# mother_card_04.net
KiCad netlist of a schematic drawn in EAGLE
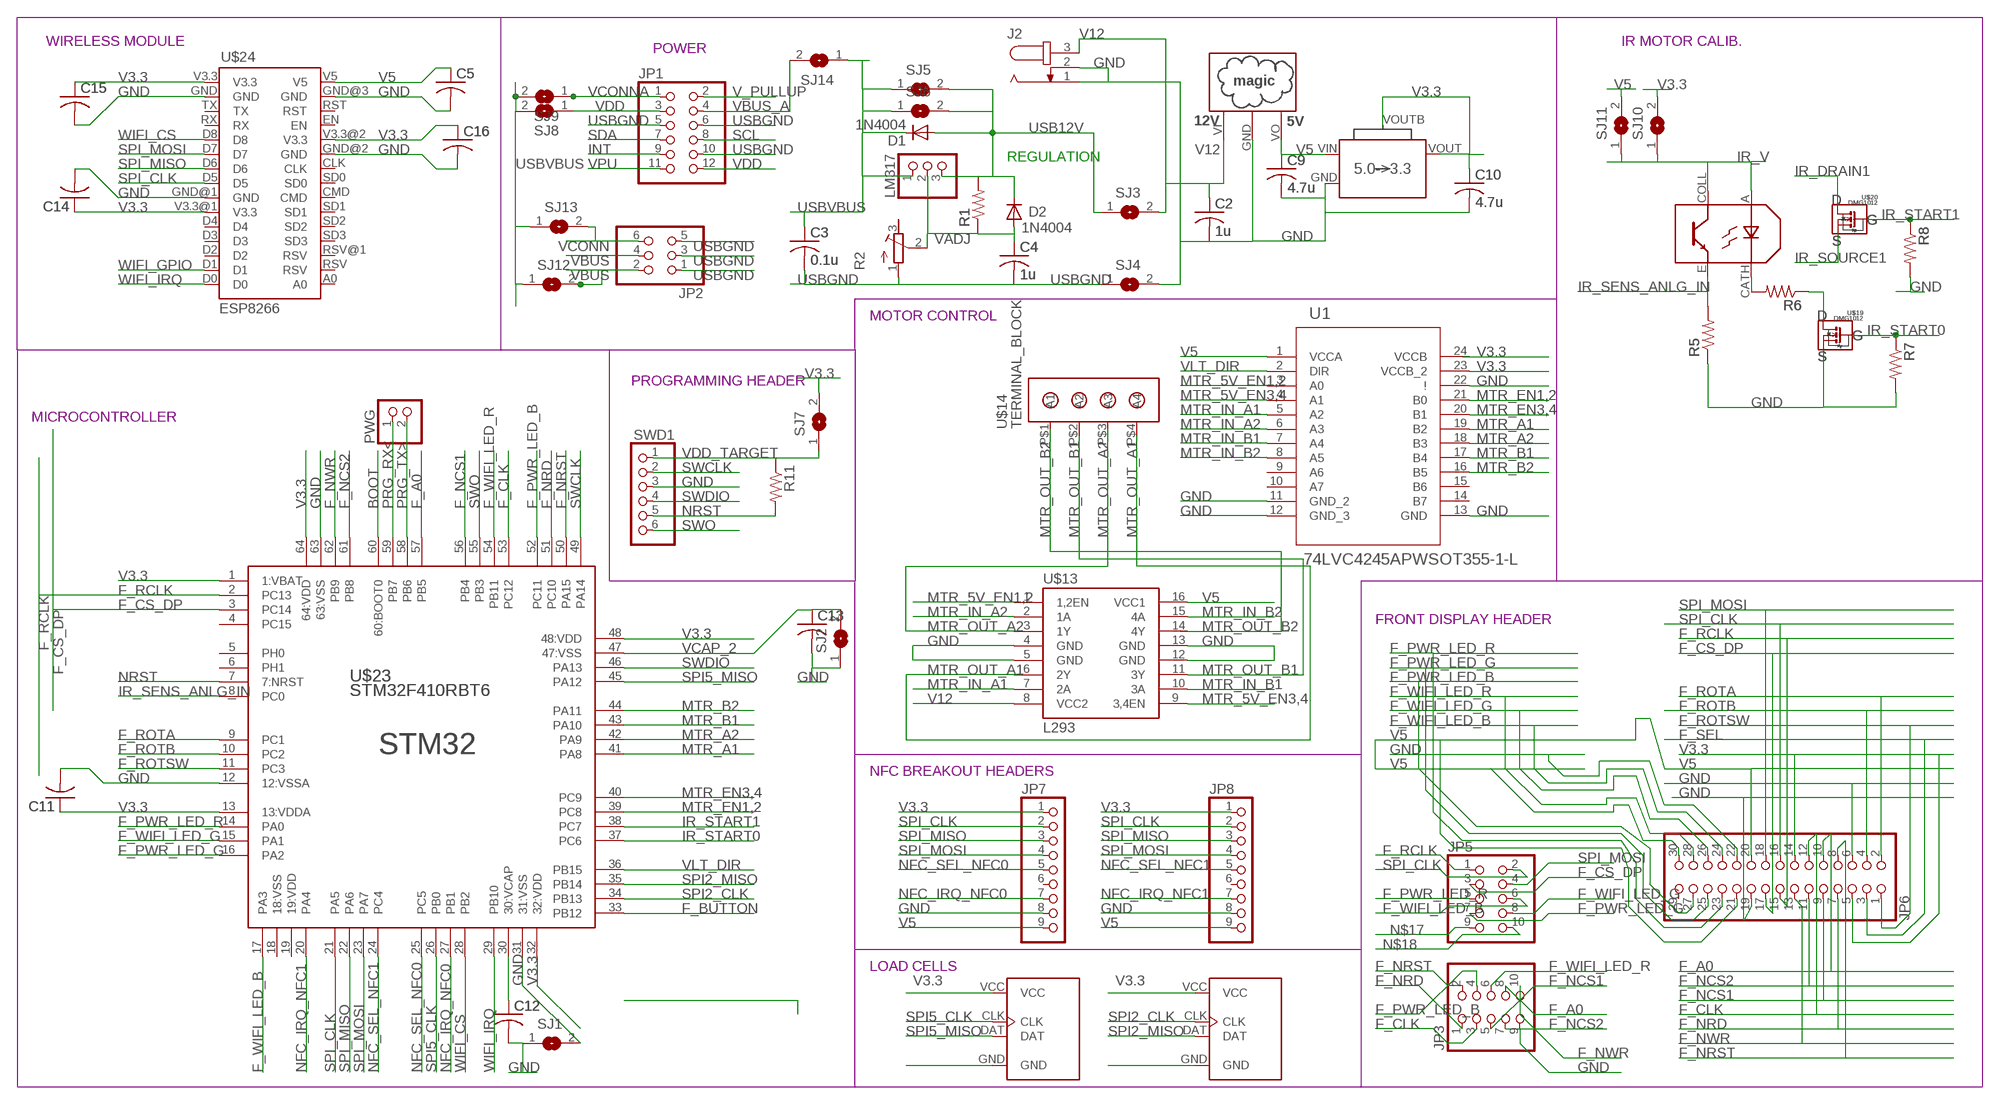
[diagram p0: schematic, sheet 1]

(export (version "E")
  (design (tool "Eeschema 10.0.6"))
  (components
    (comp (ref "C2")
      (value "1u")
      (footprint "eagle-import:C0805")
      (libsource (lib "eagle-import") (part "C-USC0805"))
    )
    (comp (ref "C3")
      (value "0.1u")
      (footprint "eagle-import:C0805")
      (libsource (lib "eagle-import") (part "C-USC0805"))
    )
    (comp (ref "C4")
      (value "1u")
      (footprint "eagle-import:C0805")
      (libsource (lib "eagle-import") (part "C-USC0805"))
    )
    (comp (ref "C5")
      (value "C-USC0805")
      (footprint "eagle-import:C0805")
      (libsource (lib "eagle-import") (part "C-USC0805"))
    )
    (comp (ref "C9")
      (value "4.7u")
      (footprint "eagle-import:C0805")
      (libsource (lib "eagle-import") (part "C-USC0805"))
    )
    (comp (ref "C10")
      (value "4.7u")
      (footprint "eagle-import:C0805")
      (libsource (lib "eagle-import") (part "C-USC0805"))
    )
    (comp (ref "C11")
      (value "C-USC0805")
      (footprint "eagle-import:C0805")
      (libsource (lib "eagle-import") (part "C-USC0805"))
    )
    (comp (ref "C12")
      (value "C-USC0805")
      (footprint "eagle-import:C0805")
      (libsource (lib "eagle-import") (part "C-USC0805"))
    )
    (comp (ref "C13")
      (value "C-USC0805")
      (footprint "eagle-import:C0805")
      (libsource (lib "eagle-import") (part "C-USC0805"))
    )
    (comp (ref "C14")
      (value "C-USC0805")
      (footprint "eagle-import:C0805")
      (libsource (lib "eagle-import") (part "C-USC0805"))
    )
    (comp (ref "C15")
      (value "C-USC0805")
      (footprint "eagle-import:C0805")
      (libsource (lib "eagle-import") (part "C-USC0805"))
    )
    (comp (ref "C16")
      (value "C-USC0805")
      (footprint "eagle-import:C0805")
      (libsource (lib "eagle-import") (part "C-USC0805"))
    )
    (comp (ref "D1")
      (value "1N4004")
      (footprint "eagle-import:DO41-10")
      (libsource (lib "eagle-import") (part "1N4004"))
    )
    (comp (ref "D2")
      (value "1N4004")
      (footprint "eagle-import:DO41-10")
      (libsource (lib "eagle-import") (part "1N4004"))
    )
    (comp (ref "J2")
      (value "JACK-PLUG0")
      (footprint "eagle-import:SPC4077")
      (libsource (lib "eagle-import") (part "JACK-PLUG0"))
    )
    (comp (ref "JP1")
      (value "PINHD-2X6")
      (footprint "eagle-import:2X06")
      (libsource (lib "eagle-import") (part "PINHD-2X6"))
    )
    (comp (ref "JP2")
      (value "PINHD-2X3")
      (footprint "eagle-import:2X03")
      (libsource (lib "eagle-import") (part "PINHD-2X3"))
    )
    (comp (ref "JP3")
      (value "PINHD-2X5")
      (footprint "eagle-import:2X05")
      (libsource (lib "eagle-import") (part "PINHD-2X5"))
    )
    (comp (ref "JP5")
      (value "PINHD-2X5")
      (footprint "eagle-import:2X05")
      (libsource (lib "eagle-import") (part "PINHD-2X5"))
    )
    (comp (ref "JP6")
      (value "PINHD-2X15/SOCK")
      (footprint "eagle-import:2X15_SOCK")
      (libsource (lib "eagle-import") (part "PINHD-2X15/SOCK"))
    )
    (comp (ref "JP7")
      (value "PINHD-1X9/90")
      (footprint "eagle-import:1X09_90")
      (libsource (lib "eagle-import") (part "PINHD-1X9/90"))
    )
    (comp (ref "JP8")
      (value "PINHD-1X9/90")
      (footprint "eagle-import:1X09_90")
      (libsource (lib "eagle-import") (part "PINHD-1X9/90"))
    )
    (comp (ref "LM317")
      (value "PINHD-1X3")
      (footprint "eagle-import:1X03")
      (libsource (lib "eagle-import") (part "PINHD-1X3"))
    )
    (comp (ref "PWG")
      (value "PINHD-1X2")
      (footprint "eagle-import:1X02")
      (libsource (lib "eagle-import") (part "PINHD-1X2"))
    )
    (comp (ref "R1")
      (value "R-US_R0805")
      (footprint "eagle-import:R0805")
      (libsource (lib "eagle-import") (part "seniorDesign_R-US_R0805"))
    )
    (comp (ref "R2")
      (value "R-TRIMM64W")
      (footprint "eagle-import:RTRIM64W")
      (libsource (lib "eagle-import") (part "R-TRIMM64W"))
    )
    (comp (ref "R5")
      (value "R-US_R0805")
      (footprint "eagle-import:R0805")
      (libsource (lib "eagle-import") (part "seniorDesign_R-US_R0805"))
    )
    (comp (ref "R6")
      (value "R-US_R0805")
      (footprint "eagle-import:R0805")
      (libsource (lib "eagle-import") (part "seniorDesign_R-US_R0805"))
    )
    (comp (ref "R7")
      (value "R-US_R0805")
      (footprint "eagle-import:R0805")
      (libsource (lib "eagle-import") (part "seniorDesign_R-US_R0805"))
    )
    (comp (ref "R8")
      (value "R-US_R0805")
      (footprint "eagle-import:R0805")
      (libsource (lib "eagle-import") (part "seniorDesign_R-US_R0805"))
    )
    (comp (ref "R11")
      (value "R-US_R0805")
      (footprint "eagle-import:R0805")
      (libsource (lib "eagle-import") (part "R-US_R0805"))
    )
    (comp (ref "SJ1") (value "SJ") (footprint "eagle-import:SJ") (libsource (lib "eagle-import") (part "SJ")))
    (comp (ref "SJ2") (value "SJ") (footprint "eagle-import:SJ") (libsource (lib "eagle-import") (part "SJ")))
    (comp (ref "SJ3") (value "SJ") (footprint "eagle-import:SJ") (libsource (lib "eagle-import") (part "SJ")))
    (comp (ref "SJ4") (value "SJ") (footprint "eagle-import:SJ") (libsource (lib "eagle-import") (part "SJ")))
    (comp (ref "SJ5") (value "SJ") (footprint "eagle-import:SJ") (libsource (lib "eagle-import") (part "SJ")))
    (comp (ref "SJ6") (value "SJ") (footprint "eagle-import:SJ") (libsource (lib "eagle-import") (part "SJ")))
    (comp (ref "SJ7") (value "SJ") (footprint "eagle-import:SJ") (libsource (lib "eagle-import") (part "SJ")))
    (comp (ref "SJ8") (value "SJ") (footprint "eagle-import:SJ") (libsource (lib "eagle-import") (part "SJ")))
    (comp (ref "SJ9") (value "SJ") (footprint "eagle-import:SJ") (libsource (lib "eagle-import") (part "SJ")))
    (comp (ref "SJ10")
      (value "SJ")
      (footprint "eagle-import:SJ")
      (libsource (lib "eagle-import") (part "SJ"))
    )
    (comp (ref "SJ11")
      (value "SJ")
      (footprint "eagle-import:SJ")
      (libsource (lib "eagle-import") (part "SJ"))
    )
    (comp (ref "SJ12")
      (value "SJ")
      (footprint "eagle-import:SJ")
      (libsource (lib "eagle-import") (part "SJ"))
    )
    (comp (ref "SJ13")
      (value "SJ")
      (footprint "eagle-import:SJ")
      (libsource (lib "eagle-import") (part "SJ"))
    )
    (comp (ref "SJ14")
      (value "SJ")
      (footprint "eagle-import:SJ")
      (libsource (lib "eagle-import") (part "SJ"))
    )
    (comp (ref "SWD1")
      (value "PINHD-1X6")
      (footprint "eagle-import:1X06")
      (libsource (lib "eagle-import") (part "PINHD-1X6"))
    )
    (comp (ref "U$13")
      (value "L293")
      (footprint "eagle-import:DIL16")
      (libsource (lib "eagle-import") (part "L293"))
    )
    (comp (ref "U$14")
      (value "TERMINAL_BLOCK")
      (footprint "eagle-import:1X4_BLOCK")
      (libsource (lib "eagle-import") (part "TERMINAL_BLOCK"))
    )
    (comp (ref "U$15")
      (value "AP2114H")
      (footprint "eagle-import:AP2114H")
      (libsource (lib "eagle-import") (part "AP2114H"))
    )
    (comp (ref "U$16")
      (value "OKI-78SR-W36")
      (footprint "eagle-import:SIP3")
      (libsource (lib "eagle-import") (part "OKI-78SR-W36"))
    )
    (comp (ref "U$18")
      (value "TCRT5000")
      (footprint "eagle-import:TCRT5000")
      (libsource (lib "eagle-import") (part "TCRT5000"))
    )
    (comp (ref "U$19")
      (value "DMG1012")
      (footprint "eagle-import:SOT323")
      (libsource (lib "eagle-import") (part "DMG1012"))
    )
    (comp (ref "U$20")
      (value "DMG1012")
      (footprint "eagle-import:SOT323")
      (libsource (lib "eagle-import") (part "DMG1012"))
    )
    (comp (ref "U$21")
      (value "HX711")
      (footprint "eagle-import:HX711")
      (libsource (lib "eagle-import") (part "HX711"))
    )
    (comp (ref "U$22")
      (value "HX711")
      (footprint "eagle-import:HX711")
      (libsource (lib "eagle-import") (part "HX711"))
    )
    (comp (ref "U$23")
      (value "STM32F410RBT6")
      (footprint "eagle-import:QFP50P1200X1200X160-64N")
      (libsource (lib "eagle-import") (part "STM32F410RBT6"))
    )
    (comp (ref "U$24")
      (value "ESP8266")
      (footprint "eagle-import:ESP8266")
      (libsource (lib "eagle-import") (part "ESP8266"))
    )
    (comp (ref "U1")
      (value "74LVC4245APWSOT355-1-L")
      (footprint "eagle-import:SOT355-1-L")
      (fields (field (name "MANUFACTURER_PART_NUMBER") "74LVC4245APW"))
      (libsource (lib "eagle-import") (part "74LVC4245APWSOT355-1-L"))
    )
  )
  (nets
    (net (code "1") (name "/BOOT") (class "Default")
      (node (ref "U$23") (pin "60") (pinfunction "60:BOOT0_60") (pintype "bidirectional"))
    )
    (net (code "2") (name "/F_A0") (class "Default")
      (node (ref "JP3") (pin "8") (pinfunction "8_8") (pintype "passive"))
      (node (ref "JP6") (pin "10") (pinfunction "10_10") (pintype "passive"))
      (node (ref "U$23") (pin "57") (pinfunction "PB5_57") (pintype "bidirectional"))
    )
    (net (code "3") (name "/F_BUTTON") (class "Default")
      (node (ref "U$23") (pin "33") (pinfunction "PB12_33") (pintype "bidirectional"))
    )
    (net (code "4") (name "/F_CLK") (class "Default")
      (node (ref "JP3") (pin "3") (pinfunction "3_3") (pintype "passive"))
      (node (ref "JP6") (pin "12") (pinfunction "12_12") (pintype "passive"))
      (node (ref "U$23") (pin "53") (pinfunction "PC12_53") (pintype "bidirectional"))
    )
    (net (code "5") (name "/F_CS_DP") (class "Default")
      (node (ref "JP5") (pin "3") (pinfunction "3_3") (pintype "passive"))
      (node (ref "JP6") (pin "17") (pinfunction "17_17") (pintype "passive"))
      (node (ref "U$23") (pin "3") (pinfunction "PC14_3") (pintype "bidirectional"))
    )
    (net (code "6") (name "/F_NCS1") (class "Default")
      (node (ref "JP3") (pin "5") (pinfunction "5_5") (pintype "passive"))
      (node (ref "JP6") (pin "9") (pinfunction "9_9") (pintype "passive"))
      (node (ref "U$23") (pin "56") (pinfunction "PB4_56") (pintype "bidirectional"))
    )
    (net (code "7") (name "/F_NCS2") (class "Default")
      (node (ref "JP3") (pin "7") (pinfunction "7_7") (pintype "passive"))
      (node (ref "JP6") (pin "11") (pinfunction "11_11") (pintype "passive"))
      (node (ref "U$23") (pin "61") (pinfunction "PB8_61") (pintype "bidirectional"))
    )
    (net (code "8") (name "/F_NRD") (class "Default")
      (node (ref "JP3") (pin "1") (pinfunction "1_1") (pintype "passive"))
      (node (ref "JP6") (pin "7") (pinfunction "7_7") (pintype "passive"))
      (node (ref "U$23") (pin "51") (pinfunction "PC10_51") (pintype "bidirectional"))
    )
    (net (code "9") (name "/F_NRST") (class "Default")
      (node (ref "JP3") (pin "2") (pinfunction "2_2") (pintype "passive"))
      (node (ref "JP6") (pin "8") (pinfunction "8_8") (pintype "passive"))
      (node (ref "U$23") (pin "50") (pinfunction "PA15_50") (pintype "bidirectional"))
    )
    (net (code "10") (name "/F_NWR") (class "Default")
      (node (ref "JP3") (pin "10") (pinfunction "10_10") (pintype "passive"))
      (node (ref "JP6") (pin "13") (pinfunction "13_13") (pintype "passive"))
      (node (ref "U$23") (pin "62") (pinfunction "PB9_62") (pintype "bidirectional"))
    )
    (net (code "11") (name "/F_PWR_LED_B") (class "Default")
      (node (ref "JP3") (pin "4") (pinfunction "4_4") (pintype "passive"))
      (node (ref "JP6") (pin "27") (pinfunction "27_27") (pintype "passive"))
      (node (ref "U$23") (pin "52") (pinfunction "PC11_52") (pintype "bidirectional"))
    )
    (net (code "12") (name "/F_PWR_LED_G") (class "Default")
      (node (ref "JP5") (pin "7") (pinfunction "7_7") (pintype "passive"))
      (node (ref "JP6") (pin "25") (pinfunction "25_25") (pintype "passive"))
      (node (ref "U$23") (pin "16") (pinfunction "PA2_16") (pintype "bidirectional"))
    )
    (net (code "13") (name "/F_PWR_LED_R") (class "Default")
      (node (ref "JP5") (pin "5") (pinfunction "5_5") (pintype "passive"))
      (node (ref "JP6") (pin "23") (pinfunction "23_23") (pintype "passive"))
      (node (ref "U$23") (pin "14") (pinfunction "PA0_14") (pintype "bidirectional"))
    )
    (net (code "14") (name "/F_RCLK") (class "Default")
      (node (ref "JP5") (pin "1") (pinfunction "1_1") (pintype "passive"))
      (node (ref "JP6") (pin "15") (pinfunction "15_15") (pintype "passive"))
      (node (ref "U$23") (pin "2") (pinfunction "PC13_2") (pintype "bidirectional"))
    )
    (net (code "15") (name "/F_ROTA") (class "Default")
      (node (ref "JP6") (pin "2") (pinfunction "2_2") (pintype "passive"))
      (node (ref "U$23") (pin "9") (pinfunction "PC1_9") (pintype "bidirectional"))
    )
    (net (code "16") (name "/F_ROTB") (class "Default")
      (node (ref "JP6") (pin "4") (pinfunction "4_4") (pintype "passive"))
      (node (ref "U$23") (pin "10") (pinfunction "PC2_10") (pintype "bidirectional"))
    )
    (net (code "17") (name "/F_ROTSW") (class "Default")
      (node (ref "JP6") (pin "1") (pinfunction "1_1") (pintype "passive"))
      (node (ref "U$23") (pin "11") (pinfunction "PC3_11") (pintype "bidirectional"))
    )
    (net (code "18") (name "/F_SEL") (class "Default")
      (node (ref "JP6") (pin "3") (pinfunction "3_3") (pintype "passive"))
    )
    (net (code "19") (name "/F_WIFI_LED_B") (class "Default")
      (node (ref "JP5") (pin "6") (pinfunction "6_6") (pintype "passive"))
      (node (ref "JP6") (pin "24") (pinfunction "24_24") (pintype "passive"))
      (node (ref "U$23") (pin "17") (pinfunction "PA3_17") (pintype "bidirectional"))
    )
    (net (code "20") (name "/F_WIFI_LED_G") (class "Default")
      (node (ref "JP5") (pin "8") (pinfunction "8_8") (pintype "passive"))
      (node (ref "JP6") (pin "26") (pinfunction "26_26") (pintype "passive"))
      (node (ref "U$23") (pin "15") (pinfunction "PA1_15") (pintype "bidirectional"))
    )
    (net (code "21") (name "/F_WIFI_LED_R") (class "Default")
      (node (ref "JP3") (pin "6") (pinfunction "6_6") (pintype "passive"))
      (node (ref "JP6") (pin "28") (pinfunction "28_28") (pintype "passive"))
      (node (ref "U$23") (pin "54") (pinfunction "PB11_54") (pintype "bidirectional"))
    )
    (net (code "22") (name "/GND") (class "Default")
      (node (ref "C10") (pin "2") (pinfunction "2_2") (pintype "passive"))
      (node (ref "C11") (pin "2") (pinfunction "2_2") (pintype "passive"))
      (node (ref "C12") (pin "2") (pinfunction "2_2") (pintype "passive"))
      (node (ref "C13") (pin "2") (pinfunction "2_2") (pintype "passive"))
      (node (ref "C14") (pin "2") (pinfunction "2_2") (pintype "passive"))
      (node (ref "C15") (pin "2") (pinfunction "2_2") (pintype "passive"))
      (node (ref "C16") (pin "2") (pinfunction "2_2") (pintype "passive"))
      (node (ref "C2") (pin "2") (pinfunction "2_2") (pintype "passive"))
      (node (ref "C5") (pin "2") (pinfunction "2_2") (pintype "passive"))
      (node (ref "C9") (pin "2") (pinfunction "2_2") (pintype "passive"))
      (node (ref "J2") (pin "1") (pinfunction "1_1") (pintype "passive"))
      (node (ref "J2") (pin "2") (pinfunction "2_2") (pintype "passive"))
      (node (ref "JP3") (pin "9") (pinfunction "9_9") (pintype "passive"))
      (node (ref "JP6") (pin "19") (pinfunction "19_19") (pintype "passive"))
      (node (ref "JP6") (pin "22") (pinfunction "22_22") (pintype "passive"))
      (node (ref "JP6") (pin "6") (pinfunction "6_6") (pintype "passive"))
      (node (ref "JP7") (pin "8") (pinfunction "8_8") (pintype "passive"))
      (node (ref "JP8") (pin "8") (pinfunction "8_8") (pintype "passive"))
      (node (ref "R5") (pin "1") (pinfunction "1_1") (pintype "passive"))
      (node (ref "R7") (pin "2") (pinfunction "2_2") (pintype "passive"))
      (node (ref "R8") (pin "2") (pinfunction "2_2") (pintype "passive"))
      (node (ref "SJ1") (pin "1") (pinfunction "1_1") (pintype "passive"))
      (node (ref "SJ1") (pin "2") (pinfunction "2_2") (pintype "passive"))
      (node (ref "SJ2") (pin "1") (pinfunction "1_1") (pintype "passive"))
      (node (ref "SJ4") (pin "2") (pinfunction "2_2") (pintype "passive"))
      (node (ref "SWD1") (pin "3") (pinfunction "3_3") (pintype "passive"))
      (node (ref "U$13") (pin "12") (pinfunction "GND_12") (pintype "bidirectional"))
      (node (ref "U$13") (pin "13") (pinfunction "GND_13") (pintype "bidirectional"))
      (node (ref "U$13") (pin "4") (pinfunction "GND_4") (pintype "bidirectional"))
      (node (ref "U$13") (pin "5") (pinfunction "GND_5") (pintype "bidirectional"))
      (node (ref "U$15") (pin "GND") (pinfunction "GND_GND") (pintype "power_in"))
      (node (ref "U$16") (pin "GND") (pinfunction "P$2_GND") (pintype "power_in"))
      (node (ref "U$19") (pin "S") (pinfunction "S_S") (pintype "bidirectional"))
      (node (ref "U$21") (pin "GND") (pinfunction "GND_GND") (pintype "power_in"))
      (node (ref "U$22") (pin "GND") (pinfunction "GND_GND") (pintype "power_in"))
      (node (ref "U$23") (pin "12") (pinfunction "12:VSSA_12") (pintype "bidirectional"))
      (node (ref "U$23") (pin "31") (pinfunction "31:VSS_31") (pintype "bidirectional"))
      (node (ref "U$23") (pin "63") (pinfunction "63:VSS_63") (pintype "bidirectional"))
      (node (ref "U$24") (pin "GND") (pinfunction "GND_GND") (pintype "bidirectional"))
      (node (ref "U$24") (pin "GND@1") (pinfunction "GND_GND@1") (pintype "bidirectional"))
      (node (ref "U$24") (pin "GND@2") (pinfunction "GND_GND@2") (pintype "bidirectional"))
      (node (ref "U$24") (pin "GND@3") (pinfunction "GND_GND@3") (pintype "bidirectional"))
      (node (ref "U1") (pin "11") (pinfunction "GND_2_11") (pintype "power_in"))
      (node (ref "U1") (pin "12") (pinfunction "GND_3_12") (pintype "power_in"))
      (node (ref "U1") (pin "13") (pinfunction "GND_13") (pintype "power_in"))
      (node (ref "U1") (pin "22") (pinfunction "~_22") (pintype "input"))
    )
    (net (code "23") (name "/INT") (class "Default")
      (node (ref "JP1") (pin "9") (pinfunction "9_9") (pintype "passive"))
    )
    (net (code "24") (name "/IR_DRAIN1") (class "Default")
      (node (ref "U$20") (pin "D") (pinfunction "D_D") (pintype "bidirectional"))
    )
    (net (code "25") (name "/IR_SENS_ANLG_IN") (class "Default")
      (node (ref "R5") (pin "2") (pinfunction "2_2") (pintype "passive"))
      (node (ref "U$18") (pin "E") (pinfunction "E_E") (pintype "bidirectional"))
      (node (ref "U$23") (pin "8") (pinfunction "PC0_8") (pintype "bidirectional"))
    )
    (net (code "26") (name "/IR_SOURCE1") (class "Default")
      (node (ref "U$20") (pin "S") (pinfunction "S_S") (pintype "bidirectional"))
    )
    (net (code "27") (name "/IR_START0") (class "Default")
      (node (ref "R7") (pin "1") (pinfunction "1_1") (pintype "passive"))
      (node (ref "U$19") (pin "G") (pinfunction "G_G") (pintype "bidirectional"))
      (node (ref "U$23") (pin "37") (pinfunction "PC6_37") (pintype "bidirectional"))
    )
    (net (code "28") (name "/IR_START1") (class "Default")
      (node (ref "R8") (pin "1") (pinfunction "1_1") (pintype "passive"))
      (node (ref "U$20") (pin "G") (pinfunction "G_G") (pintype "bidirectional"))
      (node (ref "U$23") (pin "38") (pinfunction "PC7_38") (pintype "bidirectional"))
    )
    (net (code "29") (name "/IR_V") (class "Default")
      (node (ref "SJ10") (pin "1") (pinfunction "1_1") (pintype "passive"))
      (node (ref "SJ11") (pin "1") (pinfunction "1_1") (pintype "passive"))
      (node (ref "U$18") (pin "A") (pinfunction "A_A") (pintype "bidirectional"))
      (node (ref "U$18") (pin "COLL") (pinfunction "COLL_COLL") (pintype "bidirectional"))
    )
    (net (code "30") (name "/MTR_5V_EN1,2") (class "Default")
      (node (ref "U$13") (pin "1") (pinfunction "1,2EN_1") (pintype "bidirectional"))
      (node (ref "U1") (pin "3") (pinfunction "A0_3") (pintype "bidirectional"))
    )
    (net (code "31") (name "/MTR_5V_EN3,4") (class "Default")
      (node (ref "U$13") (pin "9") (pinfunction "3,4EN_9") (pintype "bidirectional"))
      (node (ref "U1") (pin "4") (pinfunction "A1_4") (pintype "bidirectional"))
    )
    (net (code "32") (name "/MTR_A1") (class "Default")
      (node (ref "U$23") (pin "41") (pinfunction "PA8_41") (pintype "bidirectional"))
      (node (ref "U1") (pin "19") (pinfunction "B2_19") (pintype "bidirectional"))
    )
    (net (code "33") (name "/MTR_A2") (class "Default")
      (node (ref "U$23") (pin "42") (pinfunction "PA9_42") (pintype "bidirectional"))
      (node (ref "U1") (pin "18") (pinfunction "B3_18") (pintype "bidirectional"))
    )
    (net (code "34") (name "/MTR_B1") (class "Default")
      (node (ref "U$23") (pin "43") (pinfunction "PA10_43") (pintype "bidirectional"))
      (node (ref "U1") (pin "17") (pinfunction "B4_17") (pintype "bidirectional"))
    )
    (net (code "35") (name "/MTR_B2") (class "Default")
      (node (ref "U$23") (pin "44") (pinfunction "PA11_44") (pintype "bidirectional"))
      (node (ref "U1") (pin "16") (pinfunction "B5_16") (pintype "bidirectional"))
    )
    (net (code "36") (name "/MTR_EN1,2") (class "Default")
      (node (ref "U$23") (pin "39") (pinfunction "PC8_39") (pintype "bidirectional"))
      (node (ref "U1") (pin "21") (pinfunction "B0_21") (pintype "bidirectional"))
    )
    (net (code "37") (name "/MTR_EN3,4") (class "Default")
      (node (ref "U$23") (pin "40") (pinfunction "PC9_40") (pintype "bidirectional"))
      (node (ref "U1") (pin "20") (pinfunction "B1_20") (pintype "bidirectional"))
    )
    (net (code "38") (name "/MTR_IN_A1") (class "Default")
      (node (ref "U$13") (pin "7") (pinfunction "2A_7") (pintype "bidirectional"))
      (node (ref "U1") (pin "5") (pinfunction "A2_5") (pintype "bidirectional"))
    )
    (net (code "39") (name "/MTR_IN_A2") (class "Default")
      (node (ref "U$13") (pin "2") (pinfunction "1A_2") (pintype "bidirectional"))
      (node (ref "U1") (pin "6") (pinfunction "A3_6") (pintype "bidirectional"))
    )
    (net (code "40") (name "/MTR_IN_B1") (class "Default")
      (node (ref "U$13") (pin "10") (pinfunction "3A_10") (pintype "bidirectional"))
      (node (ref "U1") (pin "7") (pinfunction "A4_7") (pintype "bidirectional"))
    )
    (net (code "41") (name "/MTR_IN_B2") (class "Default")
      (node (ref "U$13") (pin "15") (pinfunction "4A_15") (pintype "bidirectional"))
      (node (ref "U1") (pin "8") (pinfunction "A5_8") (pintype "bidirectional"))
    )
    (net (code "42") (name "/MTR_OUT_A1") (class "Default")
      (node (ref "U$13") (pin "6") (pinfunction "2Y_6") (pintype "bidirectional"))
      (node (ref "U$14") (pin "P$4") (pinfunction "A4_P$4") (pintype "bidirectional"))
    )
    (net (code "43") (name "/MTR_OUT_A2") (class "Default")
      (node (ref "U$13") (pin "3") (pinfunction "1Y_3") (pintype "bidirectional"))
      (node (ref "U$14") (pin "P$3") (pinfunction "A3_P$3") (pintype "bidirectional"))
    )
    (net (code "44") (name "/MTR_OUT_B1") (class "Default")
      (node (ref "U$13") (pin "11") (pinfunction "3Y_11") (pintype "bidirectional"))
      (node (ref "U$14") (pin "P$2") (pinfunction "A2_P$2") (pintype "bidirectional"))
    )
    (net (code "45") (name "/MTR_OUT_B2") (class "Default")
      (node (ref "U$13") (pin "14") (pinfunction "4Y_14") (pintype "bidirectional"))
      (node (ref "U$14") (pin "P$1") (pinfunction "A1_P$1") (pintype "bidirectional"))
    )
    (net (code "46") (name "/N$17") (class "Default")
      (node (ref "JP5") (pin "9") (pinfunction "9_9") (pintype "passive"))
    )
    (net (code "47") (name "/N$18") (class "Default")
      (node (ref "JP5") (pin "10") (pinfunction "10_10") (pintype "passive"))
    )
    (net (code "48") (name "/NFC_IRQ_NFC0") (class "Default")
      (node (ref "JP7") (pin "7") (pinfunction "7_7") (pintype "passive"))
      (node (ref "U$23") (pin "27") (pinfunction "PB1_27") (pintype "bidirectional"))
    )
    (net (code "49") (name "/NFC_IRQ_NFC1") (class "Default")
      (node (ref "JP8") (pin "7") (pinfunction "7_7") (pintype "passive"))
      (node (ref "U$23") (pin "20") (pinfunction "PA4_20") (pintype "bidirectional"))
    )
    (net (code "50") (name "/NFC_SEL_NFC0") (class "Default")
      (node (ref "JP7") (pin "5") (pinfunction "5_5") (pintype "passive"))
      (node (ref "U$23") (pin "25") (pinfunction "PC5_25") (pintype "bidirectional"))
    )
    (net (code "51") (name "/NFC_SEL_NFC1") (class "Default")
      (node (ref "JP8") (pin "5") (pinfunction "5_5") (pintype "passive"))
      (node (ref "U$23") (pin "24") (pinfunction "PC4_24") (pintype "bidirectional"))
    )
    (net (code "52") (name "/NRST") (class "Default")
      (node (ref "R11") (pin "2") (pinfunction "2_2") (pintype "passive"))
      (node (ref "SWD1") (pin "5") (pinfunction "5_5") (pintype "passive"))
      (node (ref "U$23") (pin "7") (pinfunction "7:NRST_7") (pintype "bidirectional"))
    )
    (net (code "53") (name "/PRG_RX<") (class "Default")
      (node (ref "PWG") (pin "1") (pinfunction "1_1") (pintype "passive"))
      (node (ref "U$23") (pin "59") (pinfunction "PB7_59") (pintype "bidirectional"))
    )
    (net (code "54") (name "/PRG_TX>") (class "Default")
      (node (ref "PWG") (pin "2") (pinfunction "2_2") (pintype "passive"))
      (node (ref "U$23") (pin "58") (pinfunction "PB6_58") (pintype "bidirectional"))
    )
    (net (code "55") (name "/SCL") (class "Default")
      (node (ref "JP1") (pin "8") (pinfunction "8_8") (pintype "passive"))
    )
    (net (code "56") (name "/SDA") (class "Default")
      (node (ref "JP1") (pin "7") (pinfunction "7_7") (pintype "passive"))
    )
    (net (code "57") (name "/SPI2_CLK") (class "Default")
      (node (ref "U$22") (pin "CLK") (pinfunction "CLK_CLK") (pintype "bidirectional"))
      (node (ref "U$23") (pin "34") (pinfunction "PB13_34") (pintype "bidirectional"))
    )
    (net (code "58") (name "/SPI2_MISO") (class "Default")
      (node (ref "U$22") (pin "DAT") (pinfunction "DAT_DAT") (pintype "bidirectional"))
      (node (ref "U$23") (pin "35") (pinfunction "PB14_35") (pintype "bidirectional"))
    )
    (net (code "59") (name "/SPI5_CLK") (class "Default")
      (node (ref "U$21") (pin "CLK") (pinfunction "CLK_CLK") (pintype "bidirectional"))
      (node (ref "U$23") (pin "26") (pinfunction "PB0_26") (pintype "bidirectional"))
    )
    (net (code "60") (name "/SPI5_MISO") (class "Default")
      (node (ref "U$21") (pin "DAT") (pinfunction "DAT_DAT") (pintype "bidirectional"))
      (node (ref "U$23") (pin "45") (pinfunction "PA12_45") (pintype "bidirectional"))
    )
    (net (code "61") (name "/SPI_CLK") (class "Default")
      (node (ref "JP5") (pin "2") (pinfunction "2_2") (pintype "passive"))
      (node (ref "JP6") (pin "16") (pinfunction "16_16") (pintype "passive"))
      (node (ref "JP7") (pin "2") (pinfunction "2_2") (pintype "passive"))
      (node (ref "JP8") (pin "2") (pinfunction "2_2") (pintype "passive"))
      (node (ref "U$23") (pin "21") (pinfunction "PA5_21") (pintype "bidirectional"))
      (node (ref "U$24") (pin "D5") (pinfunction "D5_D5") (pintype "bidirectional"))
    )
    (net (code "62") (name "/SPI_MISO") (class "Default")
      (node (ref "JP7") (pin "3") (pinfunction "3_3") (pintype "passive"))
      (node (ref "JP8") (pin "3") (pinfunction "3_3") (pintype "passive"))
      (node (ref "U$23") (pin "22") (pinfunction "PA6_22") (pintype "bidirectional"))
      (node (ref "U$24") (pin "D6") (pinfunction "D6_D6") (pintype "bidirectional"))
    )
    (net (code "63") (name "/SPI_MOSI") (class "Default")
      (node (ref "JP5") (pin "4") (pinfunction "4_4") (pintype "passive"))
      (node (ref "JP6") (pin "18") (pinfunction "18_18") (pintype "passive"))
      (node (ref "JP7") (pin "4") (pinfunction "4_4") (pintype "passive"))
      (node (ref "JP8") (pin "4") (pinfunction "4_4") (pintype "passive"))
      (node (ref "U$23") (pin "23") (pinfunction "PA7_23") (pintype "bidirectional"))
      (node (ref "U$24") (pin "D7") (pinfunction "D7_D7") (pintype "bidirectional"))
    )
    (net (code "64") (name "/SWCLK") (class "Default")
      (node (ref "SWD1") (pin "2") (pinfunction "2_2") (pintype "passive"))
      (node (ref "U$23") (pin "49") (pinfunction "PA14_49") (pintype "bidirectional"))
    )
    (net (code "65") (name "/SWDIO") (class "Default")
      (node (ref "SWD1") (pin "4") (pinfunction "4_4") (pintype "passive"))
      (node (ref "U$23") (pin "46") (pinfunction "PA13_46") (pintype "bidirectional"))
    )
    (net (code "66") (name "/SWO") (class "Default")
      (node (ref "SWD1") (pin "6") (pinfunction "6_6") (pintype "passive"))
      (node (ref "U$23") (pin "55") (pinfunction "PB3_55") (pintype "bidirectional"))
    )
    (net (code "67") (name "/USB12V") (class "Default")
      (node (ref "D1") (pin "A") (pinfunction "A_A") (pintype "passive"))
      (node (ref "D2") (pin "C") (pinfunction "C_C") (pintype "passive"))
      (node (ref "LM317") (pin "3") (pinfunction "3_3") (pintype "passive"))
      (node (ref "R1") (pin "2") (pinfunction "2_2") (pintype "passive"))
      (node (ref "SJ3") (pin "1") (pinfunction "1_1") (pintype "passive"))
      (node (ref "SJ5") (pin "2") (pinfunction "2_2") (pintype "passive"))
      (node (ref "SJ6") (pin "2") (pinfunction "2_2") (pintype "passive"))
    )
    (net (code "68") (name "/USBGND") (class "Default")
      (node (ref "C3") (pin "2") (pinfunction "2_2") (pintype "passive"))
      (node (ref "C4") (pin "2") (pinfunction "2_2") (pintype "passive"))
      (node (ref "JP1") (pin "10") (pinfunction "10_10") (pintype "passive"))
      (node (ref "JP1") (pin "5") (pinfunction "5_5") (pintype "passive"))
      (node (ref "JP1") (pin "6") (pinfunction "6_6") (pintype "passive"))
      (node (ref "JP2") (pin "1") (pinfunction "1_1") (pintype "passive"))
      (node (ref "JP2") (pin "3") (pinfunction "3_3") (pintype "passive"))
      (node (ref "JP2") (pin "5") (pinfunction "5_5") (pintype "passive"))
      (node (ref "R2") (pin "1") (pinfunction "A_1") (pintype "passive"))
      (node (ref "SJ4") (pin "1") (pinfunction "1_1") (pintype "passive"))
    )
    (net (code "69") (name "/USBVBUS") (class "Default")
      (node (ref "C3") (pin "1") (pinfunction "1_1") (pintype "passive"))
      (node (ref "D1") (pin "C") (pinfunction "C_C") (pintype "passive"))
      (node (ref "LM317") (pin "1") (pinfunction "1_1") (pintype "passive"))
      (node (ref "SJ12") (pin "1") (pinfunction "1_1") (pintype "passive"))
      (node (ref "SJ13") (pin "1") (pinfunction "1_1") (pintype "passive"))
      (node (ref "SJ14") (pin "1") (pinfunction "1_1") (pintype "passive"))
      (node (ref "SJ5") (pin "1") (pinfunction "1_1") (pintype "passive"))
      (node (ref "SJ6") (pin "1") (pinfunction "1_1") (pintype "passive"))
      (node (ref "SJ8") (pin "2") (pinfunction "2_2") (pintype "passive"))
      (node (ref "SJ9") (pin "2") (pinfunction "2_2") (pintype "passive"))
    )
    (net (code "70") (name "/V3.3") (class "Default")
      (node (ref "C10") (pin "1") (pinfunction "1_1") (pintype "passive"))
      (node (ref "C11") (pin "1") (pinfunction "1_1") (pintype "passive"))
      (node (ref "C14") (pin "1") (pinfunction "1_1") (pintype "passive"))
      (node (ref "C15") (pin "1") (pinfunction "1_1") (pintype "passive"))
      (node (ref "C16") (pin "1") (pinfunction "1_1") (pintype "passive"))
      (node (ref "JP6") (pin "14") (pinfunction "14_14") (pintype "passive"))
      (node (ref "JP6") (pin "5") (pinfunction "5_5") (pintype "passive"))
      (node (ref "JP7") (pin "1") (pinfunction "1_1") (pintype "passive"))
      (node (ref "JP8") (pin "1") (pinfunction "1_1") (pintype "passive"))
      (node (ref "SJ10") (pin "2") (pinfunction "2_2") (pintype "passive"))
      (node (ref "SJ7") (pin "2") (pinfunction "2_2") (pintype "passive"))
      (node (ref "U$15") (pin "VOUT") (pinfunction "VO_VOUT") (pintype "output"))
      (node (ref "U$15") (pin "VOUTB") (pinfunction "BODY_VOUTB") (pintype "open_collector"))
      (node (ref "U$21") (pin "VCC") (pinfunction "VCC_VCC") (pintype "power_in"))
      (node (ref "U$22") (pin "VCC") (pinfunction "VCC_VCC") (pintype "power_in"))
      (node (ref "U$23") (pin "1") (pinfunction "1:VBAT_1") (pintype "bidirectional"))
      (node (ref "U$23") (pin "13") (pinfunction "13:VDDA_13") (pintype "bidirectional"))
      (node (ref "U$23") (pin "32") (pinfunction "32:VDD_32") (pintype "bidirectional"))
      (node (ref "U$23") (pin "48") (pinfunction "48:VDD_48") (pintype "bidirectional"))
      (node (ref "U$23") (pin "64") (pinfunction "64:VDD_64") (pintype "bidirectional"))
      (node (ref "U$24") (pin "V3.3") (pinfunction "V3.3_V3.3") (pintype "bidirectional"))
      (node (ref "U$24") (pin "V3.3@1") (pinfunction "V3.3_V3.3@1") (pintype "bidirectional"))
      (node (ref "U$24") (pin "V3.3@2") (pinfunction "V3.3_V3.3@2") (pintype "bidirectional"))
      (node (ref "U1") (pin "23") (pinfunction "VCCB_2_23") (pintype "power_in"))
      (node (ref "U1") (pin "24") (pinfunction "VCCB_24") (pintype "power_in"))
    )
    (net (code "71") (name "/V5") (class "Default")
      (node (ref "C5") (pin "1") (pinfunction "1_1") (pintype "passive"))
      (node (ref "C9") (pin "1") (pinfunction "1_1") (pintype "passive"))
      (node (ref "JP6") (pin "20") (pinfunction "20_20") (pintype "passive"))
      (node (ref "JP6") (pin "21") (pinfunction "21_21") (pintype "passive"))
      (node (ref "JP6") (pin "30") (pinfunction "30_30") (pintype "passive"))
      (node (ref "JP7") (pin "9") (pinfunction "9_9") (pintype "passive"))
      (node (ref "JP8") (pin "9") (pinfunction "9_9") (pintype "passive"))
      (node (ref "SJ11") (pin "2") (pinfunction "2_2") (pintype "passive"))
      (node (ref "U$13") (pin "16") (pinfunction "VCC1_16") (pintype "bidirectional"))
      (node (ref "U$15") (pin "VIN") (pinfunction "VI_VIN") (pintype "input"))
      (node (ref "U$16") (pin "VO") (pinfunction "P$3_VO") (pintype "output"))
      (node (ref "U$24") (pin "V5") (pinfunction "V5_V5") (pintype "bidirectional"))
      (node (ref "U1") (pin "1") (pinfunction "VCCA_1") (pintype "power_in"))
    )
    (net (code "72") (name "/V12") (class "Default")
      (node (ref "C2") (pin "1") (pinfunction "1_1") (pintype "passive"))
      (node (ref "J2") (pin "3") (pinfunction "3_3") (pintype "passive"))
      (node (ref "SJ3") (pin "2") (pinfunction "2_2") (pintype "passive"))
      (node (ref "U$13") (pin "8") (pinfunction "VCC2_8") (pintype "bidirectional"))
      (node (ref "U$16") (pin "VI") (pinfunction "P$1_VI") (pintype "input"))
    )
    (net (code "73") (name "/VADJ") (class "Default")
      (node (ref "C4") (pin "1") (pinfunction "1_1") (pintype "passive"))
      (node (ref "D2") (pin "A") (pinfunction "A_A") (pintype "passive"))
      (node (ref "LM317") (pin "2") (pinfunction "2_2") (pintype "passive"))
      (node (ref "R1") (pin "1") (pinfunction "1_1") (pintype "passive"))
      (node (ref "R2") (pin "2") (pinfunction "S_2") (pintype "passive"))
    )
    (net (code "74") (name "/VBUS") (class "Default")
      (node (ref "JP2") (pin "2") (pinfunction "2_2") (pintype "passive"))
      (node (ref "JP2") (pin "4") (pinfunction "4_4") (pintype "passive"))
      (node (ref "SJ12") (pin "2") (pinfunction "2_2") (pintype "passive"))
    )
    (net (code "75") (name "/VBUS_A") (class "Default")
      (node (ref "JP1") (pin "4") (pinfunction "4_4") (pintype "passive"))
      (node (ref "SJ14") (pin "2") (pinfunction "2_2") (pintype "passive"))
    )
    (net (code "76") (name "/VCAP_2") (class "Default")
      (node (ref "C13") (pin "1") (pinfunction "1_1") (pintype "passive"))
      (node (ref "SJ2") (pin "2") (pinfunction "2_2") (pintype "passive"))
      (node (ref "U$23") (pin "47") (pinfunction "47:VSS_47") (pintype "bidirectional"))
    )
    (net (code "77") (name "/VCONN") (class "Default")
      (node (ref "JP2") (pin "6") (pinfunction "6_6") (pintype "passive"))
      (node (ref "SJ13") (pin "2") (pinfunction "2_2") (pintype "passive"))
    )
    (net (code "78") (name "/VCONNA") (class "Default")
      (node (ref "JP1") (pin "1") (pinfunction "1_1") (pintype "passive"))
      (node (ref "SJ9") (pin "1") (pinfunction "1_1") (pintype "passive"))
    )
    (net (code "79") (name "/VDD") (class "Default")
      (node (ref "JP1") (pin "12") (pinfunction "12_12") (pintype "passive"))
      (node (ref "JP1") (pin "3") (pinfunction "3_3") (pintype "passive"))
      (node (ref "SJ8") (pin "1") (pinfunction "1_1") (pintype "passive"))
    )
    (net (code "80") (name "/VDD_TARGET") (class "Default")
      (node (ref "R11") (pin "1") (pinfunction "1_1") (pintype "passive"))
      (node (ref "SJ7") (pin "1") (pinfunction "1_1") (pintype "passive"))
      (node (ref "SWD1") (pin "1") (pinfunction "1_1") (pintype "passive"))
    )
    (net (code "81") (name "/VLT_DIR") (class "Default")
      (node (ref "U$23") (pin "36") (pinfunction "PB15_36") (pintype "bidirectional"))
      (node (ref "U1") (pin "2") (pinfunction "DIR_2") (pintype "input"))
    )
    (net (code "82") (name "/VPU") (class "Default")
      (node (ref "JP1") (pin "11") (pinfunction "11_11") (pintype "passive"))
    )
    (net (code "83") (name "/V_PULLUP") (class "Default")
      (node (ref "JP1") (pin "2") (pinfunction "2_2") (pintype "passive"))
    )
    (net (code "84") (name "/WIFI_CS") (class "Default")
      (node (ref "U$23") (pin "28") (pinfunction "PB2_28") (pintype "bidirectional"))
      (node (ref "U$24") (pin "D8") (pinfunction "D8_D8") (pintype "bidirectional"))
    )
    (net (code "85") (name "/WIFI_GPIO") (class "Default")
      (node (ref "U$24") (pin "D1") (pinfunction "D1_D1") (pintype "bidirectional"))
    )
    (net (code "86") (name "/WIFI_IRQ") (class "Default")
      (node (ref "U$23") (pin "29") (pinfunction "PB10_29") (pintype "bidirectional"))
      (node (ref "U$24") (pin "D0") (pinfunction "D0_D0") (pintype "bidirectional"))
    )
    (net (code "87") (name "Net-(R6-Pad1)") (class "Default")
      (node (ref "R6") (pin "1") (pinfunction "1_1") (pintype "passive"))
      (node (ref "U$19") (pin "D") (pinfunction "D_D") (pintype "bidirectional"))
    )
    (net (code "88") (name "Net-(R6-Pad2)") (class "Default")
      (node (ref "R6") (pin "2") (pinfunction "2_2") (pintype "passive"))
      (node (ref "U$18") (pin "CATH") (pinfunction "CATH_CATH") (pintype "bidirectional"))
    )
    (net (code "89") (name "Net-(U$23-30:VCAP)") (class "Default")
      (node (ref "C12") (pin "1") (pinfunction "1_1") (pintype "passive"))
      (node (ref "U$23") (pin "30") (pinfunction "30:VCAP_30") (pintype "bidirectional"))
    )
    (net (code "90") (name "unconnected-(JP6-Pad29)") (class "Default")
      (node (ref "JP6") (pin "29") (pinfunction "29_29") (pintype "passive"))
    )
    (net (code "91") (name "unconnected-(JP7-Pad6)") (class "Default")
      (node (ref "JP7") (pin "6") (pinfunction "6_6") (pintype "passive"))
    )
    (net (code "92") (name "unconnected-(JP8-Pad6)") (class "Default")
      (node (ref "JP8") (pin "6") (pinfunction "6_6") (pintype "passive"))
    )
    (net (code "93") (name "unconnected-(R2-E-Pad3)") (class "Default")
      (node (ref "R2") (pin "3") (pinfunction "E_3") (pintype "passive"))
    )
    (net (code "94") (name "unconnected-(U$23-18:VSS-Pad18)") (class "Default")
      (node (ref "U$23") (pin "18") (pinfunction "18:VSS_18") (pintype "bidirectional"))
    )
    (net (code "95") (name "unconnected-(U$23-19:VDD-Pad19)") (class "Default")
      (node (ref "U$23") (pin "19") (pinfunction "19:VDD_19") (pintype "bidirectional"))
    )
    (net (code "96") (name "unconnected-(U$23-PC15-Pad4)") (class "Default")
      (node (ref "U$23") (pin "4") (pinfunction "PC15_4") (pintype "bidirectional"))
    )
    (net (code "97") (name "unconnected-(U$23-PH0-Pad5)") (class "Default")
      (node (ref "U$23") (pin "5") (pinfunction "PH0_5") (pintype "bidirectional"))
    )
    (net (code "98") (name "unconnected-(U$23-PH1-Pad6)") (class "Default")
      (node (ref "U$23") (pin "6") (pinfunction "PH1_6") (pintype "bidirectional"))
    )
    (net (code "99") (name "unconnected-(U$24-PadA0)") (class "Default")
      (node (ref "U$24") (pin "A0") (pinfunction "A0_A0") (pintype "bidirectional"))
    )
    (net (code "100") (name "unconnected-(U$24-PadCLK)") (class "Default")
      (node (ref "U$24") (pin "CLK") (pinfunction "CLK_CLK") (pintype "bidirectional"))
    )
    (net (code "101") (name "unconnected-(U$24-PadCMD)") (class "Default")
      (node (ref "U$24") (pin "CMD") (pinfunction "CMD_CMD") (pintype "bidirectional"))
    )
    (net (code "102") (name "unconnected-(U$24-PadD2)") (class "Default")
      (node (ref "U$24") (pin "D2") (pinfunction "D2_D2") (pintype "bidirectional"))
    )
    (net (code "103") (name "unconnected-(U$24-PadD3)") (class "Default")
      (node (ref "U$24") (pin "D3") (pinfunction "D3_D3") (pintype "bidirectional"))
    )
    (net (code "104") (name "unconnected-(U$24-PadD4)") (class "Default")
      (node (ref "U$24") (pin "D4") (pinfunction "D4_D4") (pintype "bidirectional"))
    )
    (net (code "105") (name "unconnected-(U$24-PadEN)") (class "Default")
      (node (ref "U$24") (pin "EN") (pinfunction "EN_EN") (pintype "bidirectional"))
    )
    (net (code "106") (name "unconnected-(U$24-PadRST)") (class "Default")
      (node (ref "U$24") (pin "RST") (pinfunction "RST_RST") (pintype "bidirectional"))
    )
    (net (code "107") (name "unconnected-(U$24-PadRSV)") (class "Default")
      (node (ref "U$24") (pin "RSV") (pinfunction "RSV_RSV") (pintype "bidirectional"))
    )
    (net (code "108") (name "unconnected-(U$24-PadRX)") (class "Default")
      (node (ref "U$24") (pin "RX") (pinfunction "RX_RX") (pintype "bidirectional"))
    )
    (net (code "109") (name "unconnected-(U$24-PadSD0)") (class "Default")
      (node (ref "U$24") (pin "SD0") (pinfunction "SD0_SD0") (pintype "bidirectional"))
    )
    (net (code "110") (name "unconnected-(U$24-PadSD1)") (class "Default")
      (node (ref "U$24") (pin "SD1") (pinfunction "SD1_SD1") (pintype "bidirectional"))
    )
    (net (code "111") (name "unconnected-(U$24-PadSD2)") (class "Default")
      (node (ref "U$24") (pin "SD2") (pinfunction "SD2_SD2") (pintype "bidirectional"))
    )
    (net (code "112") (name "unconnected-(U$24-PadSD3)") (class "Default")
      (node (ref "U$24") (pin "SD3") (pinfunction "SD3_SD3") (pintype "bidirectional"))
    )
    (net (code "113") (name "unconnected-(U$24-PadTX)") (class "Default")
      (node (ref "U$24") (pin "TX") (pinfunction "TX_TX") (pintype "bidirectional"))
    )
    (net (code "114") (name "unconnected-(U$24-RSV-PadRSV@1)") (class "Default")
      (node (ref "U$24") (pin "RSV@1") (pinfunction "RSV_RSV@1") (pintype "bidirectional"))
    )
    (net (code "115") (name "unconnected-(U1-A6-Pad9)") (class "Default")
      (node (ref "U1") (pin "9") (pinfunction "A6_9") (pintype "bidirectional"))
    )
    (net (code "116") (name "unconnected-(U1-A7-Pad10)") (class "Default")
      (node (ref "U1") (pin "10") (pinfunction "A7_10") (pintype "bidirectional"))
    )
    (net (code "117") (name "unconnected-(U1-B6-Pad15)") (class "Default")
      (node (ref "U1") (pin "15") (pinfunction "B6_15") (pintype "bidirectional"))
    )
    (net (code "118") (name "unconnected-(U1-B7-Pad14)") (class "Default")
      (node (ref "U1") (pin "14") (pinfunction "B7_14") (pintype "bidirectional"))
    )
  )
)
